# RGB-Controller.net
KiCad netlist of a schematic drawn in EasyEDA
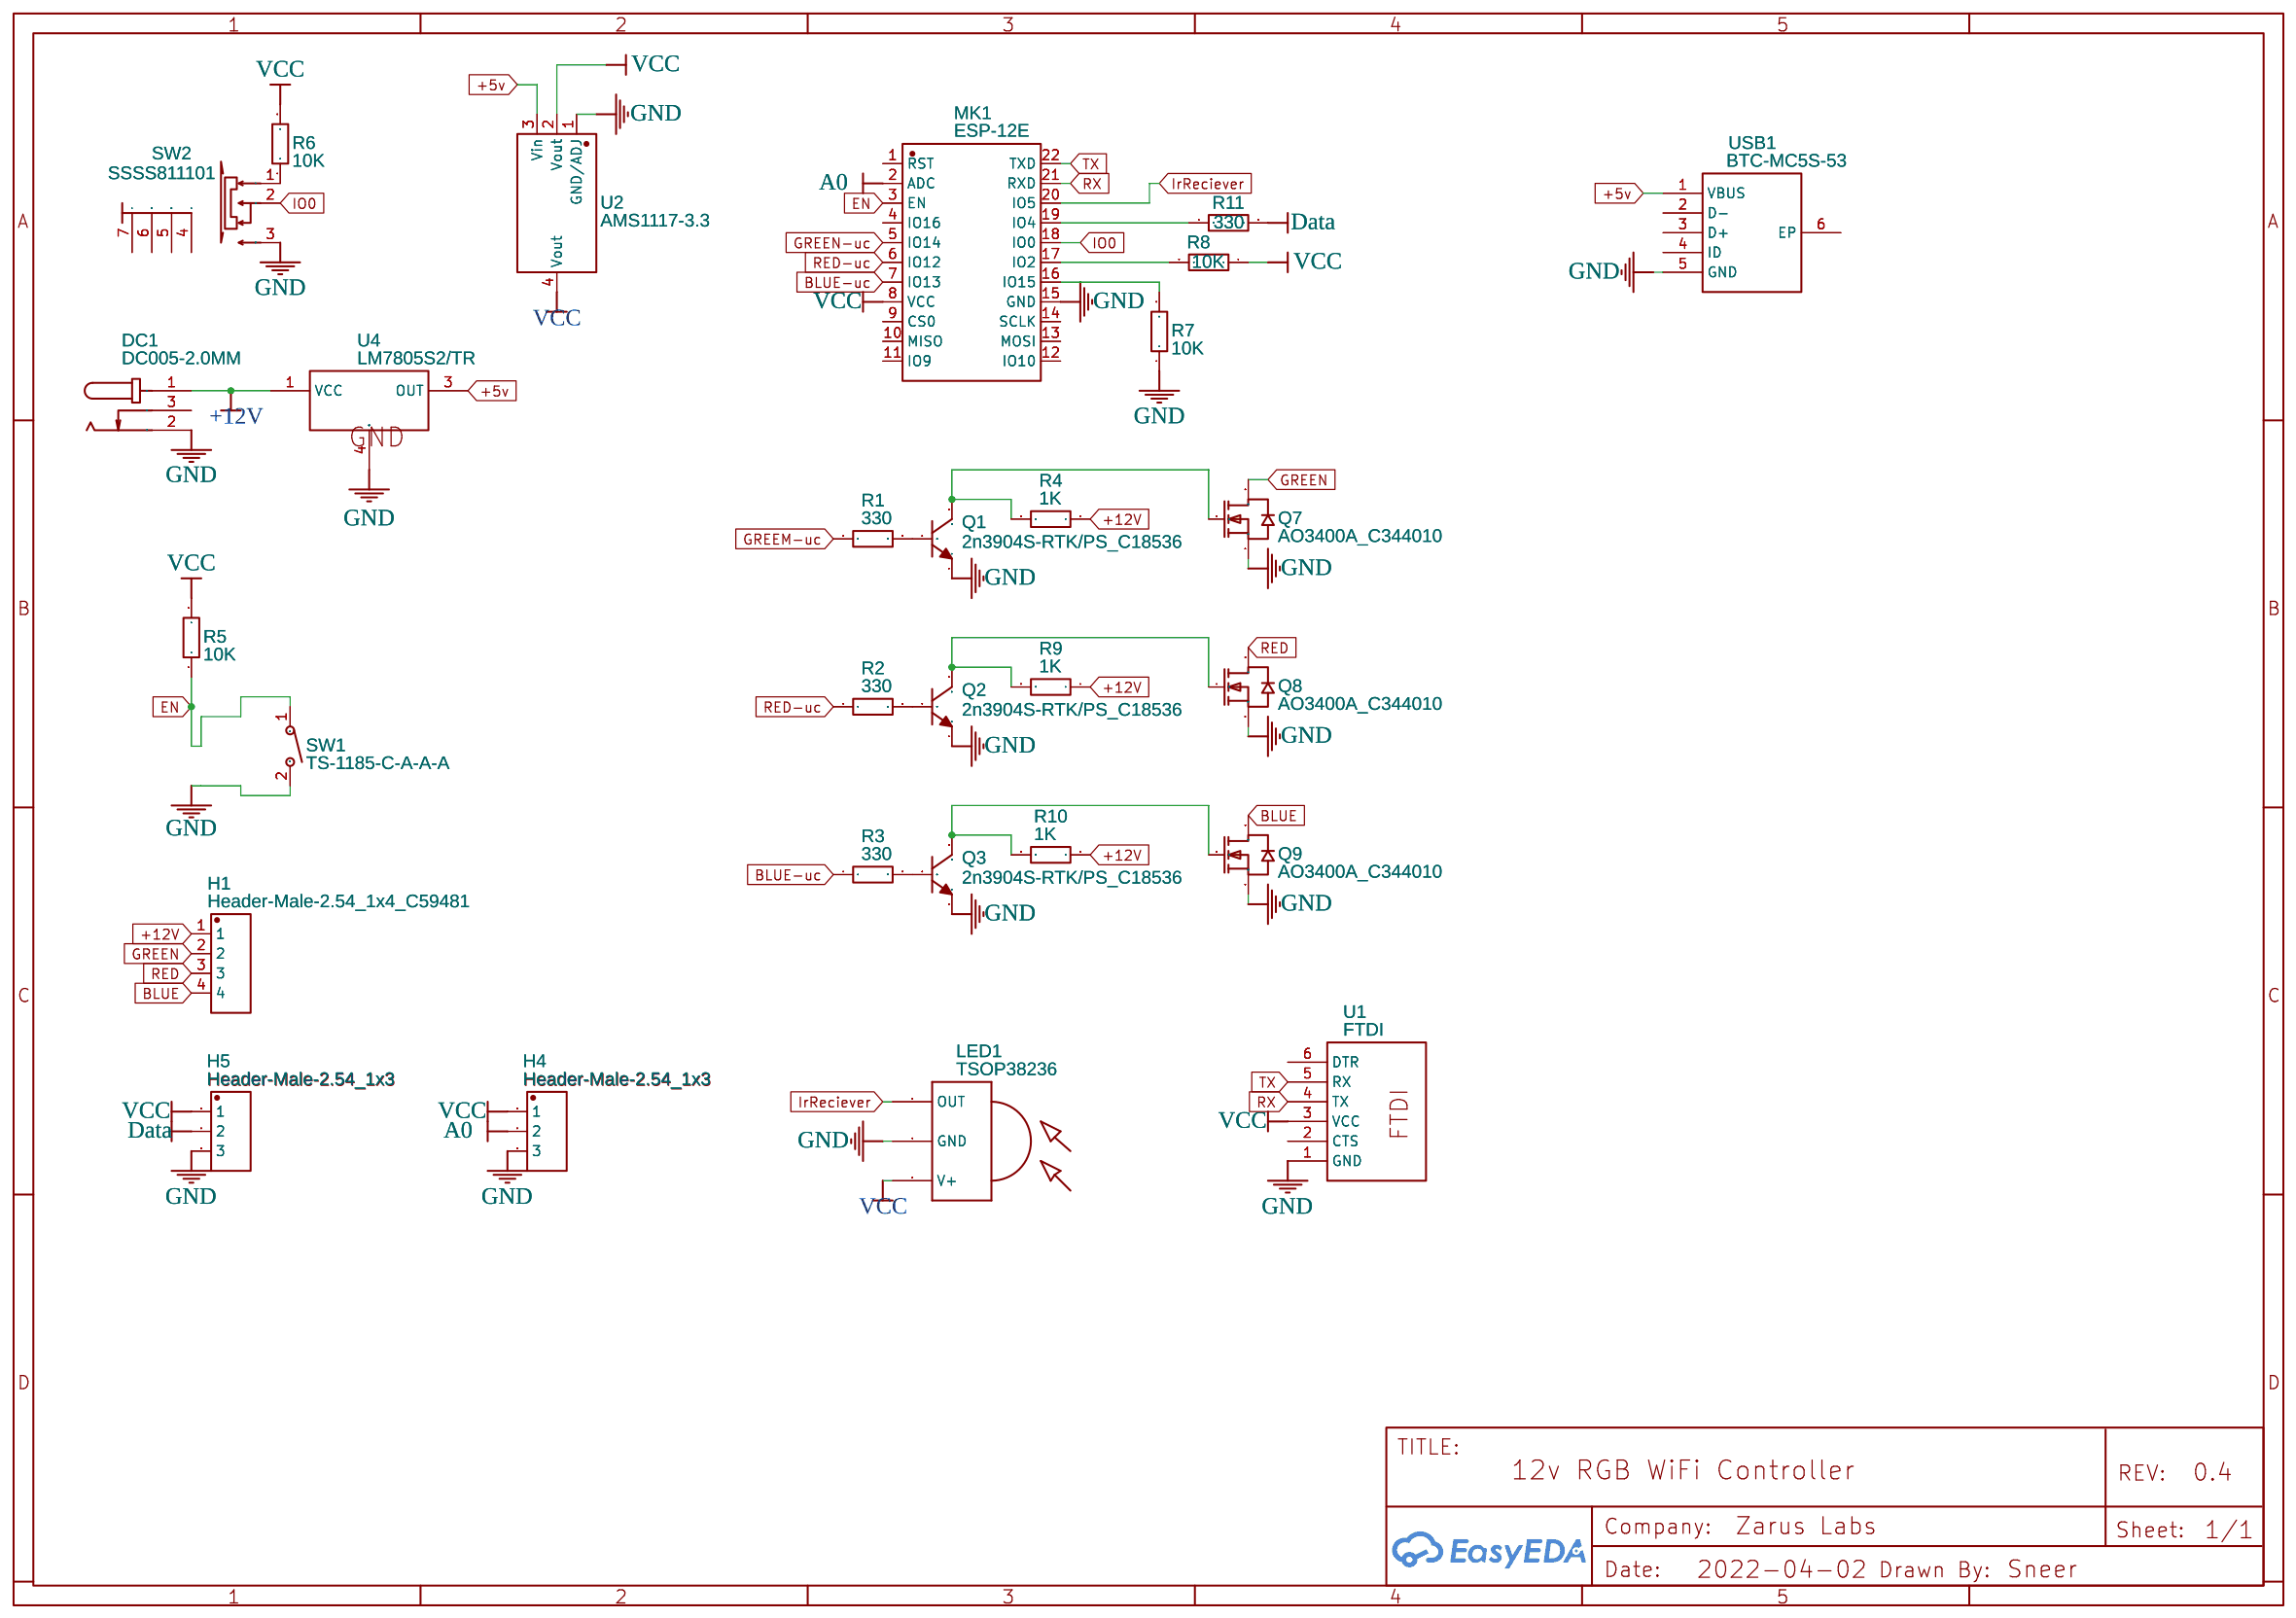
[diagram p0: schematic sheet]

(export (version "E")
  (design (tool "Eeschema 10.0.6"))
  (components
    (comp (ref "DC1")
      (value "DC005-2.0MM")
      (fields (field (name "BOM_Supplier Part") "C111567"))
      (libsource (lib "") (part "DC005-2.0MM"))
    )
    (comp (ref "H1")
      (value "Header-Male-2.54_1x4_C59481")
      (fields
        (field (name "BOM_Manufacturer Part") "Headers  Pins 1*4P")
        (field (name "BOM_Supplier Part") "C59481")
      )
      (libsource (lib "") (part "Header-Male-2.54_1x4_C59481"))
    )
    (comp (ref "H4") (value "Header-Male-2.54_1x3") (libsource (lib "") (part "Header-Male-2.54_1x3")))
    (comp (ref "H5") (value "Header-Male-2.54_1x3") (libsource (lib "") (part "Header-Male-2.54_1x3")))
    (comp (ref "LED1")
      (value "TSOP38236")
      (fields (field (name "BOM_Supplier Part") "C5139"))
      (libsource (lib "") (part "TSOP38236"))
    )
    (comp (ref "MK1")
      (value "ESP-12E")
      (fields (field (name "BOM_Supplier Part") "C89297"))
      (libsource (lib "") (part "ESP-12E"))
    )
    (comp (ref "Q1")
      (value "2n3904S-RTK/PS_C18536")
      (fields
        (field (name "BOM_Manufacturer Part") "2n3904S-RTK/PS")
        (field (name "BOM_Supplier Part") "C18536")
      )
      (libsource (lib "") (part "2n3904S-RTK/PS_C18536"))
    )
    (comp (ref "Q2")
      (value "2n3904S-RTK/PS_C18536")
      (fields
        (field (name "BOM_Manufacturer Part") "2n3904S-RTK/PS")
        (field (name "BOM_Supplier Part") "C18536")
      )
      (libsource (lib "") (part "2n3904S-RTK/PS_C18536"))
    )
    (comp (ref "Q3")
      (value "2n3904S-RTK/PS_C18536")
      (fields
        (field (name "BOM_Manufacturer Part") "2n3904S-RTK/PS")
        (field (name "BOM_Supplier Part") "C18536")
      )
      (libsource (lib "") (part "2n3904S-RTK/PS_C18536"))
    )
    (comp (ref "Q7")
      (value "AO3400A_C344010")
      (fields (field (name "BOM_Manufacturer Part") "AO3400A") (field (name "BOM_Supplier Part") "C344010"))
      (libsource (lib "") (part "AO3400A_C344010"))
    )
    (comp (ref "Q8")
      (value "AO3400A_C344010")
      (fields (field (name "BOM_Manufacturer Part") "AO3400A") (field (name "BOM_Supplier Part") "C344010"))
      (libsource (lib "") (part "AO3400A_C344010"))
    )
    (comp (ref "Q9")
      (value "AO3400A_C344010")
      (fields (field (name "BOM_Manufacturer Part") "AO3400A") (field (name "BOM_Supplier Part") "C344010"))
      (libsource (lib "") (part "AO3400A_C344010"))
    )
    (comp (ref "R1")
      (value "330")
      (fields
        (field (name "BOM_Manufacturer Part") "0805W8J0331T5E")
        (field (name "BOM_Supplier Part") "C25306")
      )
      (libsource (lib "") (part "0805W8J0331T5E"))
    )
    (comp (ref "R2")
      (value "330")
      (fields
        (field (name "BOM_Manufacturer Part") "0805W8J0331T5E")
        (field (name "BOM_Supplier Part") "C25306")
      )
      (libsource (lib "") (part "0805W8J0331T5E"))
    )
    (comp (ref "R3")
      (value "330")
      (fields
        (field (name "BOM_Manufacturer Part") "0805W8J0331T5E")
        (field (name "BOM_Supplier Part") "C25306")
      )
      (libsource (lib "") (part "0805W8J0331T5E"))
    )
    (comp (ref "R4")
      (value "1K")
      (fields
        (field (name "BOM_Manufacturer Part") "1210W3J0102T5E")
        (field (name "BOM_Supplier Part") "C25681")
      )
      (libsource (lib "") (part "1210W3J0102T5E"))
    )
    (comp (ref "R5")
      (value "10K")
      (fields
        (field (name "BOM_Manufacturer Part") "1206W4F1002T5E")
        (field (name "BOM_Supplier Part") "C17902")
      )
      (libsource (lib "") (part "1206W4F1002T5E_1"))
    )
    (comp (ref "R6")
      (value "10K")
      (fields
        (field (name "BOM_Manufacturer Part") "1206W4F1002T5E")
        (field (name "BOM_Supplier Part") "C17902")
      )
      (libsource (lib "") (part "1206W4F1002T5E_1"))
    )
    (comp (ref "R7")
      (value "10K")
      (fields
        (field (name "BOM_Manufacturer Part") "1206W4F1002T5E")
        (field (name "BOM_Supplier Part") "C17902")
      )
      (libsource (lib "") (part "1206W4F1002T5E_1"))
    )
    (comp (ref "R8")
      (value "10K")
      (fields
        (field (name "BOM_Manufacturer Part") "1206W4F1002T5E")
        (field (name "BOM_Supplier Part") "C17902")
      )
      (libsource (lib "") (part "1206W4F1002T5E"))
    )
    (comp (ref "R9")
      (value "1K")
      (fields
        (field (name "BOM_Manufacturer Part") "1210W3J0102T5E")
        (field (name "BOM_Supplier Part") "C25681")
      )
      (libsource (lib "") (part "1210W3J0102T5E"))
    )
    (comp (ref "R10")
      (value "1K")
      (fields
        (field (name "BOM_Manufacturer Part") "1210W3J0102T5E")
        (field (name "BOM_Supplier Part") "C25681")
      )
      (libsource (lib "") (part "1210W3J0102T5E"))
    )
    (comp (ref "R11")
      (value "330")
      (fields
        (field (name "BOM_Manufacturer Part") "0805W8J0331T5E")
        (field (name "BOM_Supplier Part") "C25306")
      )
      (libsource (lib "") (part "0805W8J0331T5E"))
    )
    (comp (ref "SW1")
      (value "TS-1185-C-A-A-A")
      (fields (field (name "BOM_Supplier Part") "C561518"))
      (libsource (lib "") (part "TS-1185-C-A-A-A"))
    )
    (comp (ref "SW2")
      (value "SSSS811101")
      (fields (field (name "BOM_Supplier Part") "C109335"))
      (libsource (lib "") (part "SSSS811101"))
    )
    (comp (ref "U1") (value "FTDI") (libsource (lib "") (part "FTDI")))
    (comp (ref "U2")
      (value "AMS1117-3.3")
      (fields (field (name "BOM_Supplier Part") "C6186"))
      (libsource (lib "") (part "AMS1117-3.3"))
    )
    (comp (ref "U4")
      (value "LM7805S2/TR")
      (fields (field (name "BOM_Supplier Part") "C2902505"))
      (libsource (lib "") (part "LM7805S2/TR"))
    )
    (comp (ref "USB1")
      (value "BTC-MC5S-53")
      (fields (field (name "BOM_Supplier Part") "C2908216"))
      (libsource (lib "") (part "BTC-MC5S-53"))
    )
  )
  (nets
    (net (code "1") (name "+5v") (class "Default")
      (node (ref "U2") (pin "3") (pinfunction "Vin_3") (pintype "unspecified"))
      (node (ref "U4") (pin "3") (pinfunction "OUT_3") (pintype "passive"))
      (node (ref "USB1") (pin "1") (pinfunction "VBUS_1") (pintype "unspecified"))
    )
    (net (code "2") (name "+12V") (class "Default")
      (node (ref "DC1") (pin "1") (pinfunction "1_1") (pintype "unspecified"))
      (node (ref "H1") (pin "1") (pinfunction "1_1") (pintype "unspecified"))
      (node (ref "R10") (pin "1") (pinfunction "1_1") (pintype "input"))
      (node (ref "R4") (pin "1") (pinfunction "1_1") (pintype "input"))
      (node (ref "R9") (pin "1") (pinfunction "1_1") (pintype "input"))
      (node (ref "U4") (pin "1") (pinfunction "VCC_1") (pintype "passive"))
    )
    (net (code "3") (name "A0") (class "Default")
      (node (ref "H4") (pin "2") (pinfunction "2_2") (pintype "unspecified"))
      (node (ref "MK1") (pin "2") (pinfunction "ADC_2") (pintype "unspecified"))
    )
    (net (code "4") (name "BLUE") (class "Default")
      (node (ref "H1") (pin "4") (pinfunction "4_4") (pintype "unspecified"))
      (node (ref "Q9") (pin "3") (pinfunction "D_3") (pintype "unspecified"))
    )
    (net (code "5") (name "BLUE-uc") (class "Default")
      (node (ref "MK1") (pin "7") (pinfunction "IO13_7") (pintype "unspecified"))
      (node (ref "R3") (pin "1") (pinfunction "1_1") (pintype "input"))
    )
    (net (code "6") (name "Data") (class "Default")
      (node (ref "H5") (pin "2") (pinfunction "2_2") (pintype "unspecified"))
      (node (ref "R11") (pin "2") (pinfunction "2_2") (pintype "input"))
    )
    (net (code "7") (name "EN") (class "Default")
      (node (ref "MK1") (pin "3") (pinfunction "EN_3") (pintype "unspecified"))
      (node (ref "R5") (pin "1") (pinfunction "1_1") (pintype "input"))
      (node (ref "SW1") (pin "1") (pinfunction "1_1") (pintype "unspecified"))
    )
    (net (code "8") (name "GND") (class "Default")
      (node (ref "DC1") (pin "2") (pinfunction "2_2") (pintype "unspecified"))
      (node (ref "H4") (pin "3") (pinfunction "3_3") (pintype "unspecified"))
      (node (ref "H5") (pin "3") (pinfunction "3_3") (pintype "unspecified"))
      (node (ref "LED1") (pin "2") (pinfunction "GND_2") (pintype "unspecified"))
      (node (ref "MK1") (pin "15") (pinfunction "GND_15") (pintype "unspecified"))
      (node (ref "Q1") (pin "1") (pinfunction "E_1") (pintype "input"))
      (node (ref "Q2") (pin "1") (pinfunction "E_1") (pintype "input"))
      (node (ref "Q3") (pin "1") (pinfunction "E_1") (pintype "input"))
      (node (ref "Q7") (pin "2") (pinfunction "S_2") (pintype "unspecified"))
      (node (ref "Q8") (pin "2") (pinfunction "S_2") (pintype "unspecified"))
      (node (ref "Q9") (pin "2") (pinfunction "S_2") (pintype "unspecified"))
      (node (ref "R7") (pin "1") (pinfunction "1_1") (pintype "input"))
      (node (ref "SW1") (pin "2") (pinfunction "2_2") (pintype "unspecified"))
      (node (ref "SW2") (pin "3") (pinfunction "3_3") (pintype "unspecified"))
      (node (ref "U1") (pin "1") (pinfunction "GND_1") (pintype "unspecified"))
      (node (ref "U2") (pin "1") (pinfunction "GND/ADJ_1") (pintype "unspecified"))
      (node (ref "U4") (pin "4") (pinfunction "GND_4") (pintype "passive"))
      (node (ref "USB1") (pin "5") (pinfunction "GND_5") (pintype "unspecified"))
    )
    (net (code "9") (name "GREEM-uc") (class "Default")
      (node (ref "R1") (pin "1") (pinfunction "1_1") (pintype "input"))
    )
    (net (code "10") (name "GREEN") (class "Default")
      (node (ref "H1") (pin "2") (pinfunction "2_2") (pintype "unspecified"))
      (node (ref "Q7") (pin "3") (pinfunction "D_3") (pintype "unspecified"))
    )
    (net (code "11") (name "GREEN-uc") (class "Default")
      (node (ref "MK1") (pin "5") (pinfunction "IO14_5") (pintype "unspecified"))
    )
    (net (code "12") (name "IO0") (class "Default")
      (node (ref "MK1") (pin "18") (pinfunction "IO0_18") (pintype "unspecified"))
      (node (ref "SW2") (pin "2") (pinfunction "2_2") (pintype "unspecified"))
    )
    (net (code "13") (name "IrReciever") (class "Default")
      (node (ref "LED1") (pin "1") (pinfunction "OUT_1") (pintype "unspecified"))
      (node (ref "MK1") (pin "20") (pinfunction "IO5_20") (pintype "unspecified"))
    )
    (net (code "14") (name "Net-(MK1-IO2)") (class "Default")
      (node (ref "MK1") (pin "17") (pinfunction "IO2_17") (pintype "unspecified"))
      (node (ref "R8") (pin "2") (pinfunction "2_2") (pintype "input"))
    )
    (net (code "15") (name "Net-(MK1-IO4)") (class "Default")
      (node (ref "MK1") (pin "19") (pinfunction "IO4_19") (pintype "unspecified"))
      (node (ref "R11") (pin "1") (pinfunction "1_1") (pintype "input"))
    )
    (net (code "16") (name "Net-(MK1-IO15)") (class "Default")
      (node (ref "MK1") (pin "16") (pinfunction "IO15_16") (pintype "unspecified"))
      (node (ref "R7") (pin "2") (pinfunction "2_2") (pintype "input"))
    )
    (net (code "17") (name "Net-(Q1-B)") (class "Default")
      (node (ref "Q1") (pin "2") (pinfunction "B_2") (pintype "input"))
      (node (ref "R1") (pin "2") (pinfunction "2_2") (pintype "input"))
    )
    (net (code "18") (name "Net-(Q1-C)") (class "Default")
      (node (ref "Q1") (pin "3") (pinfunction "C_3") (pintype "input"))
      (node (ref "Q7") (pin "1") (pinfunction "G_1") (pintype "unspecified"))
      (node (ref "R4") (pin "2") (pinfunction "2_2") (pintype "input"))
    )
    (net (code "19") (name "Net-(Q2-B)") (class "Default")
      (node (ref "Q2") (pin "2") (pinfunction "B_2") (pintype "input"))
      (node (ref "R2") (pin "2") (pinfunction "2_2") (pintype "input"))
    )
    (net (code "20") (name "Net-(Q2-C)") (class "Default")
      (node (ref "Q2") (pin "3") (pinfunction "C_3") (pintype "input"))
      (node (ref "Q8") (pin "1") (pinfunction "G_1") (pintype "unspecified"))
      (node (ref "R9") (pin "2") (pinfunction "2_2") (pintype "input"))
    )
    (net (code "21") (name "Net-(Q3-B)") (class "Default")
      (node (ref "Q3") (pin "2") (pinfunction "B_2") (pintype "input"))
      (node (ref "R3") (pin "2") (pinfunction "2_2") (pintype "input"))
    )
    (net (code "22") (name "Net-(Q3-C)") (class "Default")
      (node (ref "Q3") (pin "3") (pinfunction "C_3") (pintype "input"))
      (node (ref "Q9") (pin "1") (pinfunction "G_1") (pintype "unspecified"))
      (node (ref "R10") (pin "2") (pinfunction "2_2") (pintype "input"))
    )
    (net (code "23") (name "Net-(R6-Pad1)") (class "Default")
      (node (ref "R6") (pin "1") (pinfunction "1_1") (pintype "input"))
      (node (ref "SW2") (pin "1") (pinfunction "1_1") (pintype "unspecified"))
    )
    (net (code "24") (name "RED") (class "Default")
      (node (ref "H1") (pin "3") (pinfunction "3_3") (pintype "unspecified"))
      (node (ref "Q8") (pin "3") (pinfunction "D_3") (pintype "unspecified"))
    )
    (net (code "25") (name "RED-uc") (class "Default")
      (node (ref "MK1") (pin "6") (pinfunction "IO12_6") (pintype "unspecified"))
      (node (ref "R2") (pin "1") (pinfunction "1_1") (pintype "input"))
    )
    (net (code "26") (name "RX") (class "Default")
      (node (ref "MK1") (pin "21") (pinfunction "RXD_21") (pintype "unspecified"))
      (node (ref "U1") (pin "4") (pinfunction "TX_4") (pintype "unspecified"))
    )
    (net (code "27") (name "TX") (class "Default")
      (node (ref "MK1") (pin "22") (pinfunction "TXD_22") (pintype "unspecified"))
      (node (ref "U1") (pin "5") (pinfunction "RX_5") (pintype "unspecified"))
    )
    (net (code "28") (name "VCC") (class "Default")
      (node (ref "H4") (pin "1") (pinfunction "1_1") (pintype "unspecified"))
      (node (ref "H5") (pin "1") (pinfunction "1_1") (pintype "unspecified"))
      (node (ref "LED1") (pin "3") (pinfunction "V+_3") (pintype "unspecified"))
      (node (ref "MK1") (pin "8") (pinfunction "VCC_8") (pintype "unspecified"))
      (node (ref "R5") (pin "2") (pinfunction "2_2") (pintype "input"))
      (node (ref "R6") (pin "2") (pinfunction "2_2") (pintype "input"))
      (node (ref "R8") (pin "1") (pinfunction "1_1") (pintype "input"))
      (node (ref "U1") (pin "3") (pinfunction "VCC_3") (pintype "unspecified"))
      (node (ref "U2") (pin "2") (pinfunction "Vout_2") (pintype "unspecified"))
      (node (ref "U2") (pin "4") (pinfunction "Vout_4") (pintype "unspecified"))
    )
    (net (code "29") (name "unconnected-(DC1-Pad3)") (class "Default")
      (node (ref "DC1") (pin "3") (pinfunction "3_3") (pintype "unspecified"))
    )
    (net (code "30") (name "unconnected-(MK1-CS0-Pad9)") (class "Default")
      (node (ref "MK1") (pin "9") (pinfunction "CS0_9") (pintype "unspecified"))
    )
    (net (code "31") (name "unconnected-(MK1-IO9-Pad11)") (class "Default")
      (node (ref "MK1") (pin "11") (pinfunction "IO9_11") (pintype "unspecified"))
    )
    (net (code "32") (name "unconnected-(MK1-IO10-Pad12)") (class "Default")
      (node (ref "MK1") (pin "12") (pinfunction "IO10_12") (pintype "unspecified"))
    )
    (net (code "33") (name "unconnected-(MK1-IO16-Pad4)") (class "Default")
      (node (ref "MK1") (pin "4") (pinfunction "IO16_4") (pintype "unspecified"))
    )
    (net (code "34") (name "unconnected-(MK1-MISO-Pad10)") (class "Default")
      (node (ref "MK1") (pin "10") (pinfunction "MISO_10") (pintype "unspecified"))
    )
    (net (code "35") (name "unconnected-(MK1-MOSI-Pad13)") (class "Default")
      (node (ref "MK1") (pin "13") (pinfunction "MOSI_13") (pintype "unspecified"))
    )
    (net (code "36") (name "unconnected-(MK1-RST-Pad1)") (class "Default")
      (node (ref "MK1") (pin "1") (pinfunction "RST_1") (pintype "unspecified"))
    )
    (net (code "37") (name "unconnected-(MK1-SCLK-Pad14)") (class "Default")
      (node (ref "MK1") (pin "14") (pinfunction "SCLK_14") (pintype "unspecified"))
    )
    (net (code "38") (name "unconnected-(SW2-Pad4)") (class "Default")
      (node (ref "SW2") (pin "4") (pinfunction "4_4") (pintype "unspecified"))
    )
    (net (code "39") (name "unconnected-(SW2-Pad5)") (class "Default")
      (node (ref "SW2") (pin "5") (pinfunction "5_5") (pintype "unspecified"))
    )
    (net (code "40") (name "unconnected-(SW2-Pad6)") (class "Default")
      (node (ref "SW2") (pin "6") (pinfunction "6_6") (pintype "unspecified"))
    )
    (net (code "41") (name "unconnected-(SW2-Pad7)") (class "Default")
      (node (ref "SW2") (pin "7") (pinfunction "7_7") (pintype "unspecified"))
    )
    (net (code "42") (name "unconnected-(U1-CTS-Pad2)") (class "Default")
      (node (ref "U1") (pin "2") (pinfunction "CTS_2") (pintype "unspecified"))
    )
    (net (code "43") (name "unconnected-(U1-DTR-Pad6)") (class "Default")
      (node (ref "U1") (pin "6") (pinfunction "DTR_6") (pintype "unspecified"))
    )
    (net (code "44") (name "unconnected-(USB1-D+-Pad3)") (class "Default")
      (node (ref "USB1") (pin "3") (pinfunction "D+_3") (pintype "unspecified"))
    )
    (net (code "45") (name "unconnected-(USB1-D--Pad2)") (class "Default")
      (node (ref "USB1") (pin "2") (pinfunction "D-_2") (pintype "unspecified"))
    )
    (net (code "46") (name "unconnected-(USB1-EP-Pad6)") (class "Default")
      (node (ref "USB1") (pin "6") (pinfunction "EP_6") (pintype "unspecified"))
    )
    (net (code "47") (name "unconnected-(USB1-ID-Pad4)") (class "Default")
      (node (ref "USB1") (pin "4") (pinfunction "ID_4") (pintype "unspecified"))
    )
  )
)
